# PROC010C_LC_Filtering_Reference.net
KiCad netlist of a schematic drawn in Altium Designer
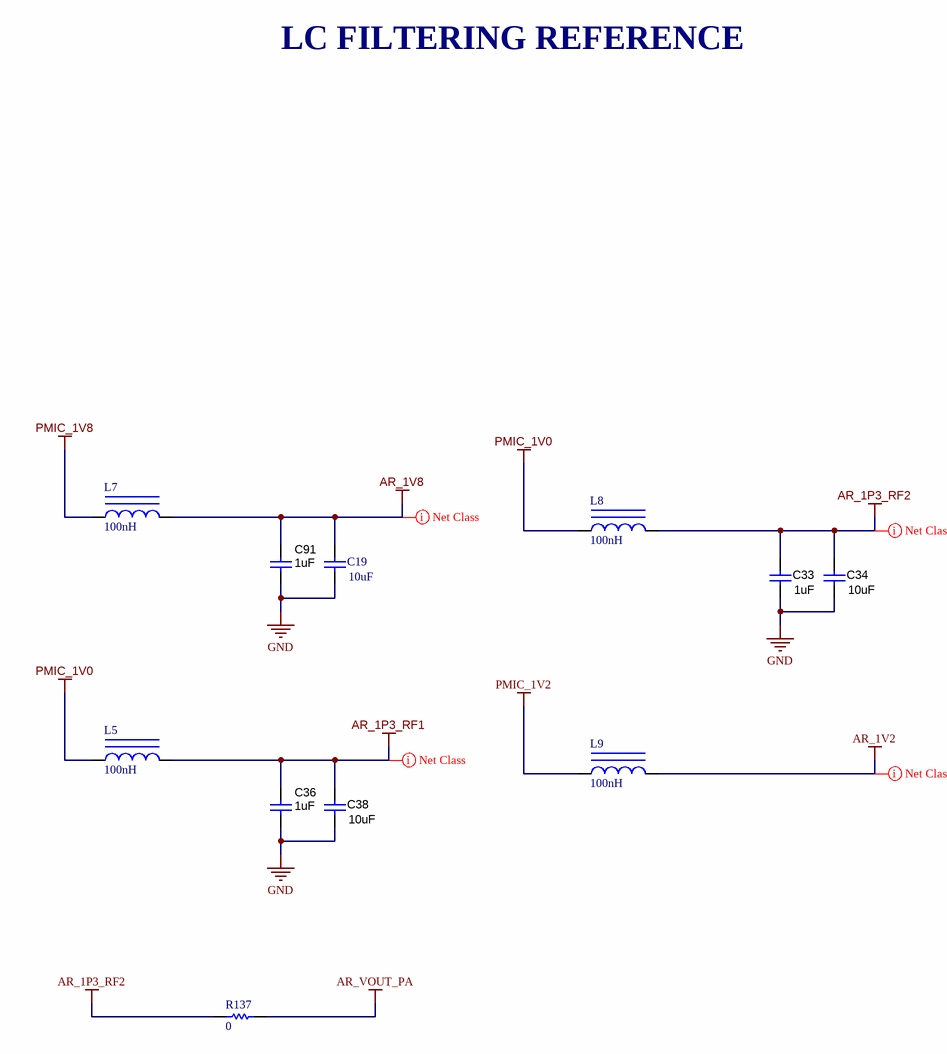
[diagram p0: PROC010C_LC_Filtering_Reference.SchDoc]

(export (version "E")
  (design (tool "Eeschema 10.0.6"))
  (components
    (comp (ref "C19")
      (value "GCM21BR71A106KE22L")
      (footprint "0805_HV")
      (description "CAP, CERM, 10 uF, 10 V, +/- 10%, X7R, 0805")
      (fields
        (field (name "MANUFACTURER") "MuRata")
        (field (name "VALUEDISPLAYED") "10uF")
        (field (name "PUBLISHER") "Texas Instruments")
      )
      (libsource (lib "Altium Vault - TI") (part "Capacitor"))
    )
    (comp (ref "C33")
      (value "GCM188R71C105KA64D")
      (footprint "0603")
      (description "CAP, CERM, 1 uF, 16 V, +/- 10%, X7R, AEC-Q200 Grade 1, 0603")
      (fields
        (field (name "MANUFACTURER") "MuRata")
        (field (name "VALUEDISPLAYED") "1uF")
        (field (name "PUBLISHER") "Texas Instruments")
      )
      (libsource (lib "Altium Vault - TI") (part "Capacitor"))
    )
    (comp (ref "C34")
      (value "GCM21BR71A106KE22L")
      (footprint "0805_HV")
      (description "CAP, CERM, 10 uF, 10 V, +/- 10%, X7R, 0805")
      (fields
        (field (name "MANUFACTURER") "MuRata")
        (field (name "VALUEDISPLAYED") "10uF")
        (field (name "PUBLISHER") "Texas Instruments")
      )
      (libsource (lib "Altium Vault - TI") (part "CMP-0008017-2"))
    )
    (comp (ref "C36")
      (value "GCM188R71C105KA64D")
      (footprint "0603")
      (description "CAP, CERM, 1 uF, 16 V, +/- 10%, X7R, AEC-Q200 Grade 1, 0603")
      (fields
        (field (name "MANUFACTURER") "MuRata")
        (field (name "VALUEDISPLAYED") "1uF")
        (field (name "PUBLISHER") "Texas Instruments")
      )
      (libsource (lib "Altium Vault - TI") (part "Capacitor"))
    )
    (comp (ref "C38")
      (value "GCM21BR71A106KE22L")
      (footprint "0805_HV")
      (description "CAP, CERM, 10 uF, 10 V, +/- 10%, X7R, 0805")
      (fields
        (field (name "MANUFACTURER") "MuRata")
        (field (name "VALUEDISPLAYED") "10uF")
        (field (name "PUBLISHER") "Texas Instruments")
      )
      (libsource (lib "Altium Vault - TI") (part "CMP-0008017-2"))
    )
    (comp (ref "C91")
      (value "GCM188R71C105KA64D")
      (footprint "0603")
      (description "CAP, CERM, 1 uF, 16 V, +/- 10%, X7R, AEC-Q200 Grade 1, 0603")
      (fields
        (field (name "MANUFACTURER") "MuRata")
        (field (name "VALUEDISPLAYED") "1uF")
        (field (name "PUBLISHER") "Texas Instruments")
      )
      (libsource (lib "Altium Vault - TI") (part "Capacitor"))
    )
    (comp (ref "L5")
      (value "NLCV32T-R10M-EFRD")
      (footprint "NLCV32")
      (description "Inductor, Wirewound, Ferrite, 100 nH, 2.85 A, 0.024 ohm, AEC-Q200 Grade 1, SMD")
      (fields (field (name "MANUFACTURER") "TDK") (field (name "VALUEDISPLAYED") "100nH"))
      (libsource (lib "Altium Vault - TI") (part "Inductor_Iron"))
    )
    (comp (ref "L7")
      (value "NLCV32T-R10M-EFRD")
      (footprint "NLCV32")
      (description "Inductor, Wirewound, Ferrite, 100 nH, 2.85 A, 0.024 ohm, AEC-Q200 Grade 1, SMD")
      (fields (field (name "MANUFACTURER") "TDK") (field (name "VALUEDISPLAYED") "100nH"))
      (libsource (lib "Altium Vault - TI") (part "Inductor_Iron"))
    )
    (comp (ref "L8")
      (value "NLCV32T-R10M-EFRD")
      (footprint "NLCV32")
      (description "Inductor, Wirewound, Ferrite, 100 nH, 2.85 A, 0.024 ohm, AEC-Q200 Grade 1, SMD")
      (fields (field (name "MANUFACTURER") "TDK") (field (name "VALUEDISPLAYED") "100nH"))
      (libsource (lib "Altium Vault - TI") (part "Inductor_Iron"))
    )
    (comp (ref "L9")
      (value "NLCV32T-R10M-EFRD")
      (footprint "NLCV32")
      (description "Inductor, Wirewound, Ferrite, 100 nH, 2.85 A, 0.024 ohm, AEC-Q200 Grade 1, SMD")
      (fields (field (name "MANUFACTURER") "TDK") (field (name "VALUEDISPLAYED") "100nH"))
      (libsource (lib "Altium Vault - TI") (part "Inductor_Iron"))
    )
    (comp (ref "R137")
      (value "MCT06030Z0000ZP500")
      (footprint "0603")
      (description "RES, 0, 5%, 0.125 W, 0603")
      (fields
        (field (name "MANUFACTURER") "Vishay/Beyschlag")
        (field (name "VALUEDISPLAYED") "0")
        (field (name "PUBLISHER") "Texas Instruments")
      )
      (libsource (lib "Altium Vault - TI") (part "CMP-0025884-3"))
    )
  )
  (nets
    (net (code "1") (name "AR_1P3_RF1") (class "Default")
      (node (ref "C36") (pin "2") (pinfunction "2_2") (pintype "passive"))
      (node (ref "C38") (pin "2") (pinfunction "2_2") (pintype "passive"))
      (node (ref "L5") (pin "2") (pinfunction "2_2") (pintype "passive"))
    )
    (net (code "2") (name "AR_1P3_RF2") (class "Default")
      (node (ref "C33") (pin "2") (pinfunction "2_2") (pintype "passive"))
      (node (ref "C34") (pin "2") (pinfunction "2_2") (pintype "passive"))
      (node (ref "L8") (pin "2") (pinfunction "2_2") (pintype "passive"))
      (node (ref "R137") (pin "1") (pinfunction "1_1") (pintype "passive"))
    )
    (net (code "3") (name "AR_1V2") (class "Default")
      (node (ref "L9") (pin "2") (pinfunction "2_2") (pintype "passive"))
    )
    (net (code "4") (name "AR_1V8") (class "Default")
      (node (ref "C19") (pin "1") (pinfunction "1_1") (pintype "passive"))
      (node (ref "C91") (pin "2") (pinfunction "2_2") (pintype "passive"))
      (node (ref "L7") (pin "2") (pinfunction "2_2") (pintype "passive"))
    )
    (net (code "5") (name "AR_VOUT_PA") (class "Default")
      (node (ref "R137") (pin "2") (pinfunction "2_2") (pintype "passive"))
    )
    (net (code "6") (name "GND") (class "Default")
      (node (ref "C19") (pin "2") (pinfunction "2_2") (pintype "passive"))
      (node (ref "C33") (pin "1") (pinfunction "1_1") (pintype "passive"))
      (node (ref "C34") (pin "1") (pinfunction "1_1") (pintype "passive"))
      (node (ref "C36") (pin "1") (pinfunction "1_1") (pintype "passive"))
      (node (ref "C38") (pin "1") (pinfunction "1_1") (pintype "passive"))
      (node (ref "C91") (pin "1") (pinfunction "1_1") (pintype "passive"))
    )
    (net (code "7") (name "PMIC_1V0") (class "Default")
      (node (ref "L5") (pin "1") (pinfunction "1_1") (pintype "passive"))
      (node (ref "L8") (pin "1") (pinfunction "1_1") (pintype "passive"))
    )
    (net (code "8") (name "PMIC_1V2") (class "Default")
      (node (ref "L9") (pin "1") (pinfunction "1_1") (pintype "passive"))
    )
    (net (code "9") (name "PMIC_1V8") (class "Default")
      (node (ref "L7") (pin "1") (pinfunction "1_1") (pintype "passive"))
    )
  )
)
